# Charge.net
KiCad netlist of a schematic drawn in Altium Designer
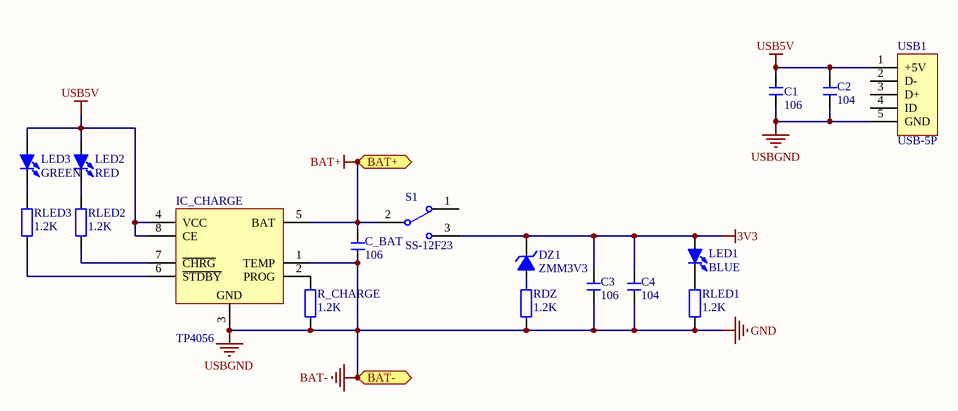
[diagram p0: Charge.SchDoc]

(export (version "E")
  (design (tool "Eeschema 10.0.6"))
  (components
    (comp (ref "C1")
      (value "106")
      (footprint "C 0805_L")
      (description "贴片电容")
      (libsource (lib "0.1 - 电阻-电容-电感") (part "C"))
    )
    (comp (ref "C2")
      (value "104")
      (footprint "C 0805_L")
      (description "贴片电容")
      (libsource (lib "0.1 - 电阻-电容-电感") (part "C"))
    )
    (comp (ref "C3")
      (value "106")
      (footprint "C 0805_L")
      (description "贴片电容")
      (libsource (lib "0.1 - 电阻-电容-电感") (part "C"))
    )
    (comp (ref "C4")
      (value "104")
      (footprint "C 0805_L")
      (description "贴片电容")
      (libsource (lib "0.1 - 电阻-电容-电感") (part "C"))
    )
    (comp (ref "C_BAT")
      (value "106")
      (footprint "C 0805_L")
      (description "贴片电容")
      (libsource (lib "0.1 - 电阻-电容-电感") (part "C"))
    )
    (comp (ref "DZ1")
      (value "ZMM3V3")
      (footprint "MINI_MELF (LL34)")
      (description "3V/0.5W稳压管")
      (fields (field (name "版权归属") "封装库来自淘宝 ID：黄晶宝石"))
      (libsource (lib "0.2 -  二极管-整流桥") (part "1N4619"))
    )
    (comp (ref "IC_CHARGE")
      (value "TP4056")
      (footprint "SOP8_N")
      (description "锂电池充电管理")
      (libsource (lib "1.1 - 电源类芯片") (part "TP4056"))
    )
    (comp (ref "LED1")
      (value "BLUE")
      (footprint "LED 0805B")
      (description "贴片LED")
      (fields (field (name "版权归属") "封装库来自淘宝 ID：黄晶宝石"))
      (libsource (lib "0.3 - LED发光二极管") (part "LED-SMD"))
    )
    (comp (ref "LED2")
      (value "RED")
      (footprint "LED 0805R")
      (description "贴片LED")
      (fields (field (name "版权归属") "封装库来自淘宝 ID：黄晶宝石"))
      (libsource (lib "0.3 - LED发光二极管") (part "LED-SMD"))
    )
    (comp (ref "LED3")
      (value "GREEN")
      (footprint "LED 0805G")
      (description "贴片LED")
      (fields (field (name "版权归属") "封装库来自淘宝 ID：黄晶宝石"))
      (libsource (lib "0.3 - LED发光二极管") (part "LED-SMD"))
    )
    (comp (ref "RDZ")
      (value "1.2K")
      (footprint "R 0805_L")
      (description "贴片电阻")
      (fields (field (name "版权归属") "来自淘宝 ID：黄晶宝石"))
      (libsource (lib "0.1 - 电阻-电容-电感") (part "R"))
    )
    (comp (ref "RLED1")
      (value "1.2K")
      (footprint "R 0805_L")
      (description "贴片电阻")
      (fields (field (name "版权归属") "来自淘宝 ID：黄晶宝石"))
      (libsource (lib "0.1 - 电阻-电容-电感") (part "R"))
    )
    (comp (ref "RLED2")
      (value "1.2K")
      (footprint "R 0805_L")
      (description "贴片电阻")
      (fields (field (name "版权归属") "来自淘宝 ID：黄晶宝石"))
      (libsource (lib "0.1 - 电阻-电容-电感") (part "R"))
    )
    (comp (ref "RLED3")
      (value "1.2K")
      (footprint "R 0805_L")
      (description "贴片电阻")
      (fields (field (name "版权归属") "来自淘宝 ID：黄晶宝石"))
      (libsource (lib "0.1 - 电阻-电容-电感") (part "R"))
    )
    (comp (ref "R_CHARGE")
      (value "1.2K")
      (footprint "R 0805_L")
      (description "贴片电阻")
      (fields (field (name "版权归属") "来自淘宝 ID：黄晶宝石"))
      (libsource (lib "0.1 - 电阻-电容-电感") (part "R"))
    )
    (comp (ref "S1")
      (value "SS-12F23")
      (footprint "MSK-12C01-07")
      (description "1路波动开关")
      (fields (field (name "版权归属") "封装库来自淘宝 ID：黄晶宝石"))
      (libsource (lib "0.7 - 常用按键-开关") (part "SSW-1P"))
    )
    (comp (ref "USB1")
      (value "USB-5P")
      (footprint "USB-MICRO_B")
      (description "微型USB母座")
      (libsource (lib "0.8 - 以太网-音频-USB插座") (part "USB-5P"))
    )
  )
  (nets
    (net (code "1") (name "3V3") (class "Default")
      (node (ref "C3") (pin "2") (pinfunction "2_2") (pintype "passive"))
      (node (ref "C4") (pin "2") (pinfunction "2_2") (pintype "passive"))
      (node (ref "DZ1") (pin "2") (pinfunction "K_2") (pintype "passive"))
      (node (ref "LED1") (pin "1") (pinfunction "A_1") (pintype "passive"))
      (node (ref "S1") (pin "3") (pinfunction "3_3") (pintype "passive"))
    )
    (net (code "2") (name "BAT+") (class "Default")
      (node (ref "C_BAT") (pin "2") (pinfunction "2_2") (pintype "passive"))
      (node (ref "IC_CHARGE") (pin "5") (pinfunction "BAT_5") (pintype "passive"))
      (node (ref "S1") (pin "2") (pinfunction "2_2") (pintype "passive"))
    )
    (net (code "3") (name "BAT-") (class "Default")
      (node (ref "C1") (pin "1") (pinfunction "1_1") (pintype "passive"))
      (node (ref "C2") (pin "1") (pinfunction "1_1") (pintype "passive"))
      (node (ref "C3") (pin "1") (pinfunction "1_1") (pintype "passive"))
      (node (ref "C4") (pin "1") (pinfunction "1_1") (pintype "passive"))
      (node (ref "C_BAT") (pin "1") (pinfunction "1_1") (pintype "passive"))
      (node (ref "IC_CHARGE") (pin "1") (pinfunction "TEMP_1") (pintype "passive"))
      (node (ref "IC_CHARGE") (pin "3") (pinfunction "GND_3") (pintype "passive"))
      (node (ref "RDZ") (pin "1") (pinfunction "1_1") (pintype "passive"))
      (node (ref "RLED1") (pin "1") (pinfunction "1_1") (pintype "passive"))
      (node (ref "R_CHARGE") (pin "1") (pinfunction "1_1") (pintype "passive"))
      (node (ref "USB1") (pin "5") (pinfunction "GND_5") (pintype "passive"))
    )
    (net (code "4") (name "Net-(DZ1-A)") (class "Default")
      (node (ref "DZ1") (pin "1") (pinfunction "A_1") (pintype "passive"))
      (node (ref "RDZ") (pin "2") (pinfunction "2_2") (pintype "passive"))
    )
    (net (code "5") (name "Net-(IC_CHARGE-PROG)") (class "Default")
      (node (ref "IC_CHARGE") (pin "2") (pinfunction "PROG_2") (pintype "passive"))
      (node (ref "R_CHARGE") (pin "2") (pinfunction "2_2") (pintype "passive"))
    )
    (net (code "6") (name "Net-(IC_CHARGE-~{CHRG})") (class "Default")
      (node (ref "IC_CHARGE") (pin "7") (pinfunction "~{CHRG}_7") (pintype "passive"))
      (node (ref "RLED2") (pin "1") (pinfunction "1_1") (pintype "passive"))
    )
    (net (code "7") (name "Net-(IC_CHARGE-~{STDBY})") (class "Default")
      (node (ref "IC_CHARGE") (pin "6") (pinfunction "~{STDBY}_6") (pintype "passive"))
      (node (ref "RLED3") (pin "1") (pinfunction "1_1") (pintype "passive"))
    )
    (net (code "8") (name "Net-(LED1-K)") (class "Default")
      (node (ref "LED1") (pin "2") (pinfunction "K_2") (pintype "passive"))
      (node (ref "RLED1") (pin "2") (pinfunction "2_2") (pintype "passive"))
    )
    (net (code "9") (name "Net-(LED2-K)") (class "Default")
      (node (ref "LED2") (pin "2") (pinfunction "K_2") (pintype "passive"))
      (node (ref "RLED2") (pin "2") (pinfunction "2_2") (pintype "passive"))
    )
    (net (code "10") (name "Net-(LED3-K)") (class "Default")
      (node (ref "LED3") (pin "2") (pinfunction "K_2") (pintype "passive"))
      (node (ref "RLED3") (pin "2") (pinfunction "2_2") (pintype "passive"))
    )
    (net (code "11") (name "USB5V") (class "Default")
      (node (ref "C1") (pin "2") (pinfunction "2_2") (pintype "passive"))
      (node (ref "C2") (pin "2") (pinfunction "2_2") (pintype "passive"))
      (node (ref "IC_CHARGE") (pin "4") (pinfunction "VCC_4") (pintype "passive"))
      (node (ref "IC_CHARGE") (pin "8") (pinfunction "CE_8") (pintype "passive"))
      (node (ref "LED2") (pin "1") (pinfunction "A_1") (pintype "passive"))
      (node (ref "LED3") (pin "1") (pinfunction "A_1") (pintype "passive"))
      (node (ref "USB1") (pin "1") (pinfunction "+5V_1") (pintype "passive"))
    )
    (net (code "12") (name "unconnected-(S1-Pad1)") (class "Default")
      (node (ref "S1") (pin "1") (pinfunction "1_1") (pintype "passive"))
    )
    (net (code "13") (name "unconnected-(USB1-D+-Pad3)") (class "Default")
      (node (ref "USB1") (pin "3") (pinfunction "D+_3") (pintype "passive"))
    )
    (net (code "14") (name "unconnected-(USB1-D--Pad2)") (class "Default")
      (node (ref "USB1") (pin "2") (pinfunction "D-_2") (pintype "passive"))
    )
    (net (code "15") (name "unconnected-(USB1-ID-Pad4)") (class "Default")
      (node (ref "USB1") (pin "4") (pinfunction "ID_4") (pintype "passive"))
    )
  )
)
